# mayfly_platform_reva.net
KiCad netlist of a schematic drawn in EAGLE
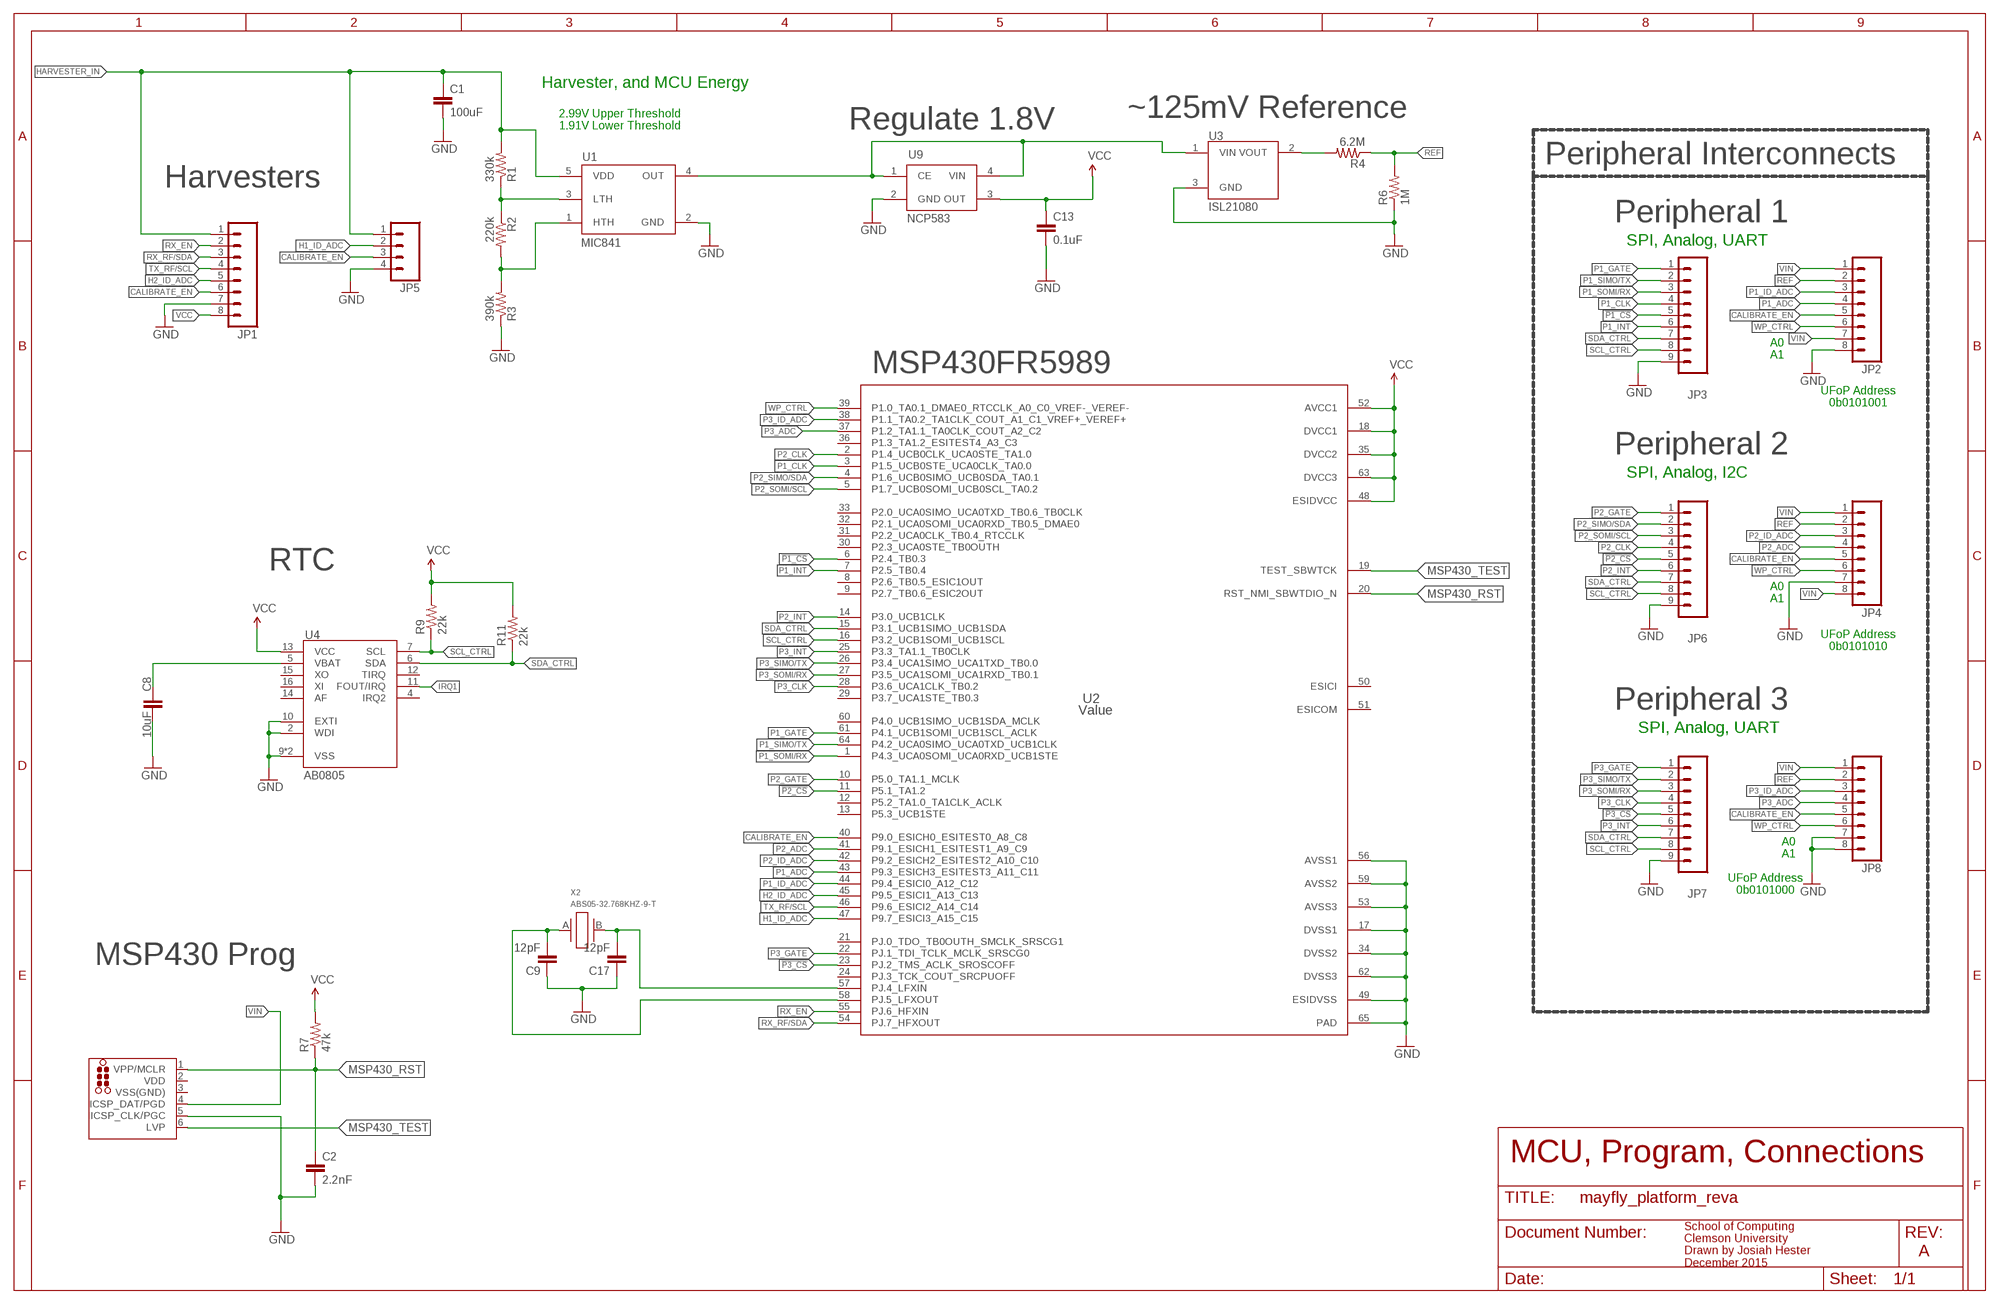
[diagram p0: schematic, sheet 1]

(export (version "E")
  (design (tool "Eeschema 10.0.6"))
  (components
    (comp (ref "C1")
      (value "100uF")
      (footprint "eagle-import:1210")
      (libsource (lib "eagle-import") (part "CAP1210"))
    )
    (comp (ref "C2")
      (value "2.2nF")
      (footprint "eagle-import:0603")
      (libsource (lib "eagle-import") (part "C-EU0603"))
    )
    (comp (ref "C8")
      (value "10uF")
      (footprint "eagle-import:0805")
      (libsource (lib "eagle-import") (part "CAP0805"))
    )
    (comp (ref "C9")
      (value "12pF")
      (footprint "eagle-import:0603")
      (libsource (lib "eagle-import") (part "C-EU0603"))
    )
    (comp (ref "C13")
      (value "0.1uF")
      (footprint "eagle-import:0603")
      (libsource (lib "eagle-import") (part "C-EU0603"))
    )
    (comp (ref "C17")
      (value "12pF")
      (footprint "eagle-import:0603")
      (libsource (lib "eagle-import") (part "C-EU0603"))
    )
    (comp (ref "J1")
      (value "TC2030-MCP-NL")
      (footprint "eagle-import:TC2030-MCP-NL")
      (libsource (lib "eagle-import") (part "TC2030-MCP-NL"))
    )
    (comp (ref "JP1")
      (value "M081.27MM")
      (footprint "eagle-import:1X08-1.27MM")
      (libsource (lib "eagle-import") (part "M081.27MM"))
    )
    (comp (ref "JP2")
      (value "M081.27MM")
      (footprint "eagle-import:1X08-1.27MM")
      (libsource (lib "eagle-import") (part "M081.27MM"))
    )
    (comp (ref "JP3")
      (value "M091.27MM")
      (footprint "eagle-import:1X09-1.27MM")
      (libsource (lib "eagle-import") (part "M091.27MM"))
    )
    (comp (ref "JP4")
      (value "M081.27MM")
      (footprint "eagle-import:1X08-1.27MM")
      (libsource (lib "eagle-import") (part "M081.27MM"))
    )
    (comp (ref "JP5")
      (value "M041.27MM")
      (footprint "eagle-import:1X04-1.27MM")
      (libsource (lib "eagle-import") (part "M041.27MM"))
    )
    (comp (ref "JP6")
      (value "M091.27MM")
      (footprint "eagle-import:1X09-1.27MM")
      (libsource (lib "eagle-import") (part "M091.27MM"))
    )
    (comp (ref "JP7")
      (value "M091.27MM")
      (footprint "eagle-import:1X09-1.27MM")
      (libsource (lib "eagle-import") (part "M091.27MM"))
    )
    (comp (ref "JP8")
      (value "M081.27MM")
      (footprint "eagle-import:1X08-1.27MM")
      (libsource (lib "eagle-import") (part "M081.27MM"))
    )
    (comp (ref "R1")
      (value "330k")
      (footprint "eagle-import:0603")
      (libsource (lib "eagle-import") (part "R-EU0603"))
    )
    (comp (ref "R2")
      (value "220k")
      (footprint "eagle-import:0603")
      (libsource (lib "eagle-import") (part "R-EU0603"))
    )
    (comp (ref "R3")
      (value "390k")
      (footprint "eagle-import:0603")
      (libsource (lib "eagle-import") (part "R-EU0603"))
    )
    (comp (ref "R4")
      (value "6.2M")
      (footprint "eagle-import:0603")
      (libsource (lib "eagle-import") (part "R-EU0603"))
    )
    (comp (ref "R6")
      (value "1M")
      (footprint "eagle-import:0603")
      (libsource (lib "eagle-import") (part "R-EU0603"))
    )
    (comp (ref "R7")
      (value "47k")
      (footprint "eagle-import:0603")
      (libsource (lib "eagle-import") (part "R-EU0603"))
    )
    (comp (ref "R9")
      (value "22k")
      (footprint "eagle-import:0603")
      (libsource (lib "eagle-import") (part "R-EU0603"))
    )
    (comp (ref "R11")
      (value "22k")
      (footprint "eagle-import:0603")
      (libsource (lib "eagle-import") (part "R-EU0603"))
    )
    (comp (ref "U1")
      (value "MIC841")
      (footprint "eagle-import:SC70-5")
      (libsource (lib "eagle-import") (part "MIC841"))
    )
    (comp (ref "U2")
      (value "Value")
      (footprint "eagle-import:RGC0064B")
      (fields
        (field (name "ALTERNATEPARTNUMBER") "MSP430FR5989IRGCT")
        (field (name "MANUFACTURER") "Texas Instruments")
        (field (name "PARTNUMBER") "MSP430FR5989IRGCR")
      )
      (libsource (lib "eagle-import") (part "MSP430FR5989IRGCR"))
    )
    (comp (ref "U3")
      (value "ISL21080")
      (footprint "eagle-import:SOT-23")
      (libsource (lib "eagle-import") (part "ISL21080"))
    )
    (comp (ref "U4")
      (value "AB0805")
      (footprint "eagle-import:QFN16")
      (libsource (lib "eagle-import") (part "AB0805"))
    )
    (comp (ref "U9")
      (value "NCP583")
      (footprint "eagle-import:SC82-AB_1PRIMARY")
      (libsource (lib "eagle-import") (part "NCP583"))
    )
    (comp (ref "X2")
      (value "ABS05-32.768KHZ-9-T")
      (footprint "eagle-import:ABS05")
      (libsource (lib "eagle-import") (part "ABS05-32.768KHZ-9-T"))
    )
  )
  (nets
    (net (code "1") (name "/VDD") (class "Default")
      (node (ref "J1") (pin "2") (pinfunction "VDD_2") (pintype "power_in"))
    )
    (net (code "2") (name "/VSS(GND)") (class "Default")
      (node (ref "J1") (pin "3") (pinfunction "VSS(GND)_3") (pintype "power_in"))
    )
    (net (code "3") (name "/~{P1_CS}") (class "Default")
      (node (ref "JP3") (pin "5") (pinfunction "5_5") (pintype "passive"))
      (node (ref "U2") (pin "6") (pinfunction "P2.4_TB0.3_6") (pintype "bidirectional"))
    )
    (net (code "4") (name "/~{P2_CS}") (class "Default")
      (node (ref "JP6") (pin "5") (pinfunction "5_5") (pintype "passive"))
      (node (ref "U2") (pin "11") (pinfunction "P5.1_TA1.2_11") (pintype "bidirectional"))
    )
    (net (code "5") (name "/~{P3_CS}") (class "Default")
      (node (ref "JP7") (pin "5") (pinfunction "5_5") (pintype "passive"))
      (node (ref "U2") (pin "23") (pinfunction "PJ.2_TMS_ACLK_SROSCOFF_23") (pintype "bidirectional"))
    )
    (net (code "6") (name "CALIBRATE_EN") (class "Default")
      (node (ref "JP1") (pin "6") (pinfunction "6_6") (pintype "passive"))
      (node (ref "JP2") (pin "5") (pinfunction "5_5") (pintype "passive"))
      (node (ref "JP4") (pin "5") (pinfunction "5_5") (pintype "passive"))
      (node (ref "JP5") (pin "3") (pinfunction "3_3") (pintype "passive"))
      (node (ref "JP8") (pin "5") (pinfunction "5_5") (pintype "passive"))
      (node (ref "U2") (pin "40") (pinfunction "P9.0_ESICH0_ESITEST0_A8_C8_40") (pintype "bidirectional"))
    )
    (net (code "7") (name "GND") (class "Default")
      (node (ref "C1") (pin "2") (pinfunction "2_2") (pintype "passive"))
      (node (ref "C13") (pin "2") (pinfunction "2_2") (pintype "passive"))
      (node (ref "C17") (pin "1") (pinfunction "1_1") (pintype "passive"))
      (node (ref "C2") (pin "2") (pinfunction "2_2") (pintype "passive"))
      (node (ref "C8") (pin "2") (pinfunction "2_2") (pintype "passive"))
      (node (ref "C9") (pin "1") (pinfunction "1_1") (pintype "passive"))
      (node (ref "J1") (pin "5") (pinfunction "ICSP_CLK/PGC_5") (pintype "output"))
      (node (ref "JP1") (pin "7") (pinfunction "7_7") (pintype "passive"))
      (node (ref "JP2") (pin "8") (pinfunction "8_8") (pintype "passive"))
      (node (ref "JP3") (pin "9") (pinfunction "9_9") (pintype "passive"))
      (node (ref "JP4") (pin "7") (pinfunction "7_7") (pintype "passive"))
      (node (ref "JP5") (pin "4") (pinfunction "4_4") (pintype "passive"))
      (node (ref "JP6") (pin "9") (pinfunction "9_9") (pintype "passive"))
      (node (ref "JP7") (pin "9") (pinfunction "9_9") (pintype "passive"))
      (node (ref "JP8") (pin "7") (pinfunction "7_7") (pintype "passive"))
      (node (ref "JP8") (pin "8") (pinfunction "8_8") (pintype "passive"))
      (node (ref "R3") (pin "1") (pinfunction "1_1") (pintype "passive"))
      (node (ref "R6") (pin "1") (pinfunction "1_1") (pintype "passive"))
      (node (ref "U1") (pin "2") (pinfunction "GND_2") (pintype "bidirectional"))
      (node (ref "U2") (pin "17") (pinfunction "DVSS1_17") (pintype "power_in"))
      (node (ref "U2") (pin "34") (pinfunction "DVSS2_34") (pintype "power_in"))
      (node (ref "U2") (pin "49") (pinfunction "ESIDVSS_49") (pintype "power_in"))
      (node (ref "U2") (pin "53") (pinfunction "AVSS3_53") (pintype "power_in"))
      (node (ref "U2") (pin "56") (pinfunction "AVSS1_56") (pintype "power_in"))
      (node (ref "U2") (pin "59") (pinfunction "AVSS2_59") (pintype "power_in"))
      (node (ref "U2") (pin "62") (pinfunction "DVSS3_62") (pintype "power_in"))
      (node (ref "U2") (pin "65") (pinfunction "PAD_65") (pintype "power_in"))
      (node (ref "U3") (pin "3") (pinfunction "GND_3") (pintype "bidirectional"))
      (node (ref "U4") (pin "10") (pinfunction "EXTI_10") (pintype "bidirectional"))
      (node (ref "U4") (pin "2") (pinfunction "WDI_2") (pintype "bidirectional"))
      (node (ref "U4") (pin "9") (pinfunction "VSS_9") (pintype "bidirectional"))
      (node (ref "U4") (pin "TH") (pinfunction "VSS_TH") (pintype "bidirectional"))
      (node (ref "U9") (pin "2") (pinfunction "GND_2") (pintype "bidirectional"))
    )
    (net (code "8") (name "H1_ID_ADC") (class "Default")
      (node (ref "JP5") (pin "2") (pinfunction "2_2") (pintype "passive"))
      (node (ref "U2") (pin "47") (pinfunction "P9.7_ESICI3_A15_C15_47") (pintype "bidirectional"))
    )
    (net (code "9") (name "H2_ID_ADC") (class "Default")
      (node (ref "JP1") (pin "5") (pinfunction "5_5") (pintype "passive"))
      (node (ref "U2") (pin "45") (pinfunction "P9.5_ESICI1_A13_C13_45") (pintype "bidirectional"))
    )
    (net (code "10") (name "HARVESTER_IN") (class "Default")
      (node (ref "C1") (pin "1") (pinfunction "1_1") (pintype "passive"))
      (node (ref "JP1") (pin "1") (pinfunction "1_1") (pintype "passive"))
      (node (ref "JP5") (pin "1") (pinfunction "1_1") (pintype "passive"))
      (node (ref "R1") (pin "2") (pinfunction "2_2") (pintype "passive"))
      (node (ref "U1") (pin "5") (pinfunction "VDD_5") (pintype "bidirectional"))
    )
    (net (code "11") (name "IRQ1") (class "Default")
      (node (ref "U4") (pin "11") (pinfunction "FOUT/IRQ_11") (pintype "bidirectional"))
    )
    (net (code "12") (name "MSP430_RST") (class "Default")
      (node (ref "C2") (pin "1") (pinfunction "1_1") (pintype "passive"))
      (node (ref "J1") (pin "1") (pinfunction "VPP/MCLR_1") (pintype "passive"))
      (node (ref "R7") (pin "1") (pinfunction "1_1") (pintype "passive"))
      (node (ref "U2") (pin "20") (pinfunction "RST_NMI_SBWTDIO_N_20") (pintype "bidirectional"))
    )
    (net (code "13") (name "MSP430_TEST") (class "Default")
      (node (ref "J1") (pin "6") (pinfunction "LVP_6") (pintype "bidirectional"))
      (node (ref "U2") (pin "19") (pinfunction "TEST_SBWTCK_19") (pintype "input"))
    )
    (net (code "14") (name "Net-(U1-HTH)") (class "Default")
      (node (ref "R2") (pin "2") (pinfunction "2_2") (pintype "passive"))
      (node (ref "R3") (pin "2") (pinfunction "2_2") (pintype "passive"))
      (node (ref "U1") (pin "1") (pinfunction "HTH_1") (pintype "bidirectional"))
    )
    (net (code "15") (name "Net-(U1-LTH)") (class "Default")
      (node (ref "R1") (pin "1") (pinfunction "1_1") (pintype "passive"))
      (node (ref "R2") (pin "1") (pinfunction "1_1") (pintype "passive"))
      (node (ref "U1") (pin "3") (pinfunction "LTH_3") (pintype "bidirectional"))
    )
    (net (code "16") (name "Net-(U2-PJ.4_LFXIN)") (class "Default")
      (node (ref "C17") (pin "2") (pinfunction "2_2") (pintype "passive"))
      (node (ref "U2") (pin "57") (pinfunction "PJ.4_LFXIN_57") (pintype "bidirectional"))
      (node (ref "X2") (pin "B") (pinfunction "2_B") (pintype "bidirectional"))
    )
    (net (code "17") (name "Net-(U2-PJ.5_LFXOUT)") (class "Default")
      (node (ref "C9") (pin "2") (pinfunction "2_2") (pintype "passive"))
      (node (ref "U2") (pin "58") (pinfunction "PJ.5_LFXOUT_58") (pintype "bidirectional"))
      (node (ref "X2") (pin "A") (pinfunction "1_A") (pintype "bidirectional"))
    )
    (net (code "18") (name "Net-(U3-VOUT)") (class "Default")
      (node (ref "R4") (pin "2") (pinfunction "2_2") (pintype "passive"))
      (node (ref "U3") (pin "2") (pinfunction "VOUT_2") (pintype "bidirectional"))
    )
    (net (code "19") (name "Net-(U4-VBAT)") (class "Default")
      (node (ref "C8") (pin "1") (pinfunction "1_1") (pintype "passive"))
      (node (ref "U4") (pin "5") (pinfunction "VBAT_5") (pintype "bidirectional"))
    )
    (net (code "20") (name "P1_ADC") (class "Default")
      (node (ref "JP2") (pin "4") (pinfunction "4_4") (pintype "passive"))
      (node (ref "U2") (pin "43") (pinfunction "P9.3_ESICH3_ESITEST3_A11_C11_43") (pintype "bidirectional"))
    )
    (net (code "21") (name "P1_CLK") (class "Default")
      (node (ref "JP3") (pin "4") (pinfunction "4_4") (pintype "passive"))
      (node (ref "U2") (pin "3") (pinfunction "P1.5_UCB0STE_UCA0CLK_TA0.0_3") (pintype "bidirectional"))
    )
    (net (code "22") (name "P1_GATE") (class "Default")
      (node (ref "JP3") (pin "1") (pinfunction "1_1") (pintype "passive"))
      (node (ref "U2") (pin "61") (pinfunction "P4.1_UCB1SOMI_UCB1SCL_ACLK_61") (pintype "bidirectional"))
    )
    (net (code "23") (name "P1_ID_ADC") (class "Default")
      (node (ref "JP2") (pin "3") (pinfunction "3_3") (pintype "passive"))
      (node (ref "U2") (pin "44") (pinfunction "P9.4_ESICI0_A12_C12_44") (pintype "bidirectional"))
    )
    (net (code "24") (name "P1_INT") (class "Default")
      (node (ref "JP3") (pin "6") (pinfunction "6_6") (pintype "passive"))
      (node (ref "U2") (pin "7") (pinfunction "P2.5_TB0.4_7") (pintype "bidirectional"))
    )
    (net (code "25") (name "P1_SIMO{slash}TX") (class "Default")
      (node (ref "JP3") (pin "2") (pinfunction "2_2") (pintype "passive"))
      (node (ref "U2") (pin "64") (pinfunction "P4.2_UCA0SIMO_UCA0TXD_UCB1CLK_64") (pintype "bidirectional"))
    )
    (net (code "26") (name "P1_SOMI{slash}RX") (class "Default")
      (node (ref "JP3") (pin "3") (pinfunction "3_3") (pintype "passive"))
      (node (ref "U2") (pin "1") (pinfunction "P4.3_UCA0SOMI_UCA0RXD_UCB1STE_1") (pintype "bidirectional"))
    )
    (net (code "27") (name "P2_ADC") (class "Default")
      (node (ref "JP4") (pin "4") (pinfunction "4_4") (pintype "passive"))
      (node (ref "U2") (pin "41") (pinfunction "P9.1_ESICH1_ESITEST1_A9_C9_41") (pintype "bidirectional"))
    )
    (net (code "28") (name "P2_CLK") (class "Default")
      (node (ref "JP6") (pin "4") (pinfunction "4_4") (pintype "passive"))
      (node (ref "U2") (pin "2") (pinfunction "P1.4_UCB0CLK_UCA0STE_TA1.0_2") (pintype "bidirectional"))
    )
    (net (code "29") (name "P2_GATE") (class "Default")
      (node (ref "JP6") (pin "1") (pinfunction "1_1") (pintype "passive"))
      (node (ref "U2") (pin "10") (pinfunction "P5.0_TA1.1_MCLK_10") (pintype "bidirectional"))
    )
    (net (code "30") (name "P2_ID_ADC") (class "Default")
      (node (ref "JP4") (pin "3") (pinfunction "3_3") (pintype "passive"))
      (node (ref "U2") (pin "42") (pinfunction "P9.2_ESICH2_ESITEST2_A10_C10_42") (pintype "bidirectional"))
    )
    (net (code "31") (name "P2_INT") (class "Default")
      (node (ref "JP6") (pin "6") (pinfunction "6_6") (pintype "passive"))
      (node (ref "U2") (pin "14") (pinfunction "P3.0_UCB1CLK_14") (pintype "bidirectional"))
    )
    (net (code "32") (name "P2_SIMO{slash}SDA") (class "Default")
      (node (ref "JP6") (pin "2") (pinfunction "2_2") (pintype "passive"))
      (node (ref "U2") (pin "4") (pinfunction "P1.6_UCB0SIMO_UCB0SDA_TA0.1_4") (pintype "bidirectional"))
    )
    (net (code "33") (name "P2_SOMI{slash}SCL") (class "Default")
      (node (ref "JP6") (pin "3") (pinfunction "3_3") (pintype "passive"))
      (node (ref "U2") (pin "5") (pinfunction "P1.7_UCB0SOMI_UCB0SCL_TA0.2_5") (pintype "bidirectional"))
    )
    (net (code "34") (name "P3_ADC") (class "Default")
      (node (ref "JP8") (pin "4") (pinfunction "4_4") (pintype "passive"))
      (node (ref "U2") (pin "37") (pinfunction "P1.2_TA1.1_TA0CLK_COUT_A2_C2_37") (pintype "bidirectional"))
    )
    (net (code "35") (name "P3_CLK") (class "Default")
      (node (ref "JP7") (pin "4") (pinfunction "4_4") (pintype "passive"))
      (node (ref "U2") (pin "28") (pinfunction "P3.6_UCA1CLK_TB0.2_28") (pintype "bidirectional"))
    )
    (net (code "36") (name "P3_GATE") (class "Default")
      (node (ref "JP7") (pin "1") (pinfunction "1_1") (pintype "passive"))
      (node (ref "U2") (pin "22") (pinfunction "PJ.1_TDI_TCLK_MCLK_SRSCG0_22") (pintype "bidirectional"))
    )
    (net (code "37") (name "P3_ID_ADC") (class "Default")
      (node (ref "JP8") (pin "3") (pinfunction "3_3") (pintype "passive"))
      (node (ref "U2") (pin "38") (pinfunction "P1.1_TA0.2_TA1CLK_COUT_A1_C1_VREF+_VEREF+_38") (pintype "bidirectional"))
    )
    (net (code "38") (name "P3_INT") (class "Default")
      (node (ref "JP7") (pin "6") (pinfunction "6_6") (pintype "passive"))
      (node (ref "U2") (pin "25") (pinfunction "P3.3_TA1.1_TB0CLK_25") (pintype "bidirectional"))
    )
    (net (code "39") (name "P3_SIMO{slash}TX") (class "Default")
      (node (ref "JP7") (pin "2") (pinfunction "2_2") (pintype "passive"))
      (node (ref "U2") (pin "26") (pinfunction "P3.4_UCA1SIMO_UCA1TXD_TB0.0_26") (pintype "bidirectional"))
    )
    (net (code "40") (name "P3_SOMI{slash}RX") (class "Default")
      (node (ref "JP7") (pin "3") (pinfunction "3_3") (pintype "passive"))
      (node (ref "U2") (pin "27") (pinfunction "P3.5_UCA1SOMI_UCA1RXD_TB0.1_27") (pintype "bidirectional"))
    )
    (net (code "41") (name "REF") (class "Default")
      (node (ref "JP2") (pin "2") (pinfunction "2_2") (pintype "passive"))
      (node (ref "JP4") (pin "2") (pinfunction "2_2") (pintype "passive"))
      (node (ref "JP8") (pin "2") (pinfunction "2_2") (pintype "passive"))
      (node (ref "R4") (pin "1") (pinfunction "1_1") (pintype "passive"))
      (node (ref "R6") (pin "2") (pinfunction "2_2") (pintype "passive"))
    )
    (net (code "42") (name "RX_EN") (class "Default")
      (node (ref "JP1") (pin "2") (pinfunction "2_2") (pintype "passive"))
      (node (ref "U2") (pin "55") (pinfunction "PJ.6_HFXIN_55") (pintype "bidirectional"))
    )
    (net (code "43") (name "RX_RF{slash}SDA") (class "Default")
      (node (ref "JP1") (pin "3") (pinfunction "3_3") (pintype "passive"))
      (node (ref "U2") (pin "54") (pinfunction "PJ.7_HFXOUT_54") (pintype "bidirectional"))
    )
    (net (code "44") (name "SCL_CTRL") (class "Default")
      (node (ref "JP3") (pin "8") (pinfunction "8_8") (pintype "passive"))
      (node (ref "JP6") (pin "8") (pinfunction "8_8") (pintype "passive"))
      (node (ref "JP7") (pin "8") (pinfunction "8_8") (pintype "passive"))
      (node (ref "R9") (pin "1") (pinfunction "1_1") (pintype "passive"))
      (node (ref "U2") (pin "16") (pinfunction "P3.2_UCB1SOMI_UCB1SCL_16") (pintype "bidirectional"))
      (node (ref "U4") (pin "7") (pinfunction "SCL_7") (pintype "bidirectional"))
    )
    (net (code "45") (name "SDA_CTRL") (class "Default")
      (node (ref "JP3") (pin "7") (pinfunction "7_7") (pintype "passive"))
      (node (ref "JP6") (pin "7") (pinfunction "7_7") (pintype "passive"))
      (node (ref "JP7") (pin "7") (pinfunction "7_7") (pintype "passive"))
      (node (ref "R11") (pin "1") (pinfunction "1_1") (pintype "passive"))
      (node (ref "U2") (pin "15") (pinfunction "P3.1_UCB1SIMO_UCB1SDA_15") (pintype "bidirectional"))
      (node (ref "U4") (pin "6") (pinfunction "SDA_6") (pintype "bidirectional"))
    )
    (net (code "46") (name "TX_RF{slash}SCL") (class "Default")
      (node (ref "JP1") (pin "4") (pinfunction "4_4") (pintype "passive"))
      (node (ref "U2") (pin "46") (pinfunction "P9.6_ESICI2_A14_C14_46") (pintype "bidirectional"))
    )
    (net (code "47") (name "VCC") (class "Default")
      (node (ref "C13") (pin "1") (pinfunction "1_1") (pintype "passive"))
      (node (ref "JP1") (pin "8") (pinfunction "8_8") (pintype "passive"))
      (node (ref "R11") (pin "2") (pinfunction "2_2") (pintype "passive"))
      (node (ref "R7") (pin "2") (pinfunction "2_2") (pintype "passive"))
      (node (ref "R9") (pin "2") (pinfunction "2_2") (pintype "passive"))
      (node (ref "U2") (pin "18") (pinfunction "DVCC1_18") (pintype "power_in"))
      (node (ref "U2") (pin "35") (pinfunction "DVCC2_35") (pintype "power_in"))
      (node (ref "U2") (pin "48") (pinfunction "ESIDVCC_48") (pintype "power_in"))
      (node (ref "U2") (pin "52") (pinfunction "AVCC1_52") (pintype "power_in"))
      (node (ref "U2") (pin "63") (pinfunction "DVCC3_63") (pintype "power_in"))
      (node (ref "U4") (pin "13") (pinfunction "VCC_13") (pintype "bidirectional"))
      (node (ref "U9") (pin "3") (pinfunction "OUT_3") (pintype "bidirectional"))
    )
    (net (code "48") (name "VIN") (class "Default")
      (node (ref "J1") (pin "4") (pinfunction "ICSP_DAT/PGD_4") (pintype "bidirectional"))
      (node (ref "JP2") (pin "1") (pinfunction "1_1") (pintype "passive"))
      (node (ref "JP2") (pin "7") (pinfunction "7_7") (pintype "passive"))
      (node (ref "JP4") (pin "1") (pinfunction "1_1") (pintype "passive"))
      (node (ref "JP4") (pin "8") (pinfunction "8_8") (pintype "passive"))
      (node (ref "JP8") (pin "1") (pinfunction "1_1") (pintype "passive"))
      (node (ref "U1") (pin "4") (pinfunction "OUT_4") (pintype "bidirectional"))
      (node (ref "U3") (pin "1") (pinfunction "VIN_1") (pintype "bidirectional"))
      (node (ref "U9") (pin "1") (pinfunction "CE_1") (pintype "bidirectional"))
      (node (ref "U9") (pin "4") (pinfunction "VIN_4") (pintype "bidirectional"))
    )
    (net (code "49") (name "WP_CTRL") (class "Default")
      (node (ref "JP2") (pin "6") (pinfunction "6_6") (pintype "passive"))
      (node (ref "JP4") (pin "6") (pinfunction "6_6") (pintype "passive"))
      (node (ref "JP8") (pin "6") (pinfunction "6_6") (pintype "passive"))
      (node (ref "U2") (pin "39") (pinfunction "P1.0_TA0.1_DMAE0_RTCCLK_A0_C0_VREF-_VEREF-_39") (pintype "bidirectional"))
    )
    (net (code "50") (name "unconnected-(U2-ESICI-Pad50)") (class "Default")
      (node (ref "U2") (pin "50") (pinfunction "ESICI_50") (pintype "input"))
    )
    (net (code "51") (name "unconnected-(U2-ESICOM-Pad51)") (class "Default")
      (node (ref "U2") (pin "51") (pinfunction "ESICOM_51") (pintype "passive"))
    )
    (net (code "52") (name "unconnected-(U2-P1.3_TA1.2_ESITEST4_A3_C3-Pad36)") (class "Default")
      (node (ref "U2") (pin "36") (pinfunction "P1.3_TA1.2_ESITEST4_A3_C3_36") (pintype "bidirectional"))
    )
    (net (code "53") (name "unconnected-(U2-P2.0_UCA0SIMO_UCA0TXD_TB0.6_TB0CLK-Pad33)") (class "Default")
      (node (ref "U2") (pin "33") (pinfunction "P2.0_UCA0SIMO_UCA0TXD_TB0.6_TB0CLK_33") (pintype "bidirectional"))
    )
    (net (code "54") (name "unconnected-(U2-P2.1_UCA0SOMI_UCA0RXD_TB0.5_DMAE0-Pad32)") (class "Default")
      (node (ref "U2") (pin "32") (pinfunction "P2.1_UCA0SOMI_UCA0RXD_TB0.5_DMAE0_32") (pintype "bidirectional"))
    )
    (net (code "55") (name "unconnected-(U2-P2.2_UCA0CLK_TB0.4_RTCCLK-Pad31)") (class "Default")
      (node (ref "U2") (pin "31") (pinfunction "P2.2_UCA0CLK_TB0.4_RTCCLK_31") (pintype "bidirectional"))
    )
    (net (code "56") (name "unconnected-(U2-P2.3_UCA0STE_TB0OUTH-Pad30)") (class "Default")
      (node (ref "U2") (pin "30") (pinfunction "P2.3_UCA0STE_TB0OUTH_30") (pintype "bidirectional"))
    )
    (net (code "57") (name "unconnected-(U2-P2.6_TB0.5_ESIC1OUT-Pad8)") (class "Default")
      (node (ref "U2") (pin "8") (pinfunction "P2.6_TB0.5_ESIC1OUT_8") (pintype "bidirectional"))
    )
    (net (code "58") (name "unconnected-(U2-P2.7_TB0.6_ESIC2OUT-Pad9)") (class "Default")
      (node (ref "U2") (pin "9") (pinfunction "P2.7_TB0.6_ESIC2OUT_9") (pintype "bidirectional"))
    )
    (net (code "59") (name "unconnected-(U2-P3.7_UCA1STE_TB0.3-Pad29)") (class "Default")
      (node (ref "U2") (pin "29") (pinfunction "P3.7_UCA1STE_TB0.3_29") (pintype "bidirectional"))
    )
    (net (code "60") (name "unconnected-(U2-P4.0_UCB1SIMO_UCB1SDA_MCLK-Pad60)") (class "Default")
      (node (ref "U2") (pin "60") (pinfunction "P4.0_UCB1SIMO_UCB1SDA_MCLK_60") (pintype "bidirectional"))
    )
    (net (code "61") (name "unconnected-(U2-P5.2_TA1.0_TA1CLK_ACLK-Pad12)") (class "Default")
      (node (ref "U2") (pin "12") (pinfunction "P5.2_TA1.0_TA1CLK_ACLK_12") (pintype "bidirectional"))
    )
    (net (code "62") (name "unconnected-(U2-P5.3_UCB1STE-Pad13)") (class "Default")
      (node (ref "U2") (pin "13") (pinfunction "P5.3_UCB1STE_13") (pintype "bidirectional"))
    )
    (net (code "63") (name "unconnected-(U2-PJ.0_TDO_TB0OUTH_SMCLK_SRSCG1-Pad21)") (class "Default")
      (node (ref "U2") (pin "21") (pinfunction "PJ.0_TDO_TB0OUTH_SMCLK_SRSCG1_21") (pintype "bidirectional"))
    )
    (net (code "64") (name "unconnected-(U2-PJ.3_TCK_COUT_SRCPUOFF-Pad24)") (class "Default")
      (node (ref "U2") (pin "24") (pinfunction "PJ.3_TCK_COUT_SRCPUOFF_24") (pintype "bidirectional"))
    )
    (net (code "65") (name "unconnected-(U4-AF-Pad14)") (class "Default")
      (node (ref "U4") (pin "14") (pinfunction "AF_14") (pintype "bidirectional"))
    )
    (net (code "66") (name "unconnected-(U4-IRQ2-Pad4)") (class "Default")
      (node (ref "U4") (pin "4") (pinfunction "IRQ2_4") (pintype "bidirectional"))
    )
    (net (code "67") (name "unconnected-(U4-TIRQ-Pad12)") (class "Default")
      (node (ref "U4") (pin "12") (pinfunction "TIRQ_12") (pintype "bidirectional"))
    )
    (net (code "68") (name "unconnected-(U4-XI-Pad16)") (class "Default")
      (node (ref "U4") (pin "16") (pinfunction "XI_16") (pintype "bidirectional"))
    )
    (net (code "69") (name "unconnected-(U4-XO-Pad15)") (class "Default")
      (node (ref "U4") (pin "15") (pinfunction "XO_15") (pintype "bidirectional"))
    )
  )
)
